# M784new.net
KiCad netlist of a schematic drawn in EAGLE
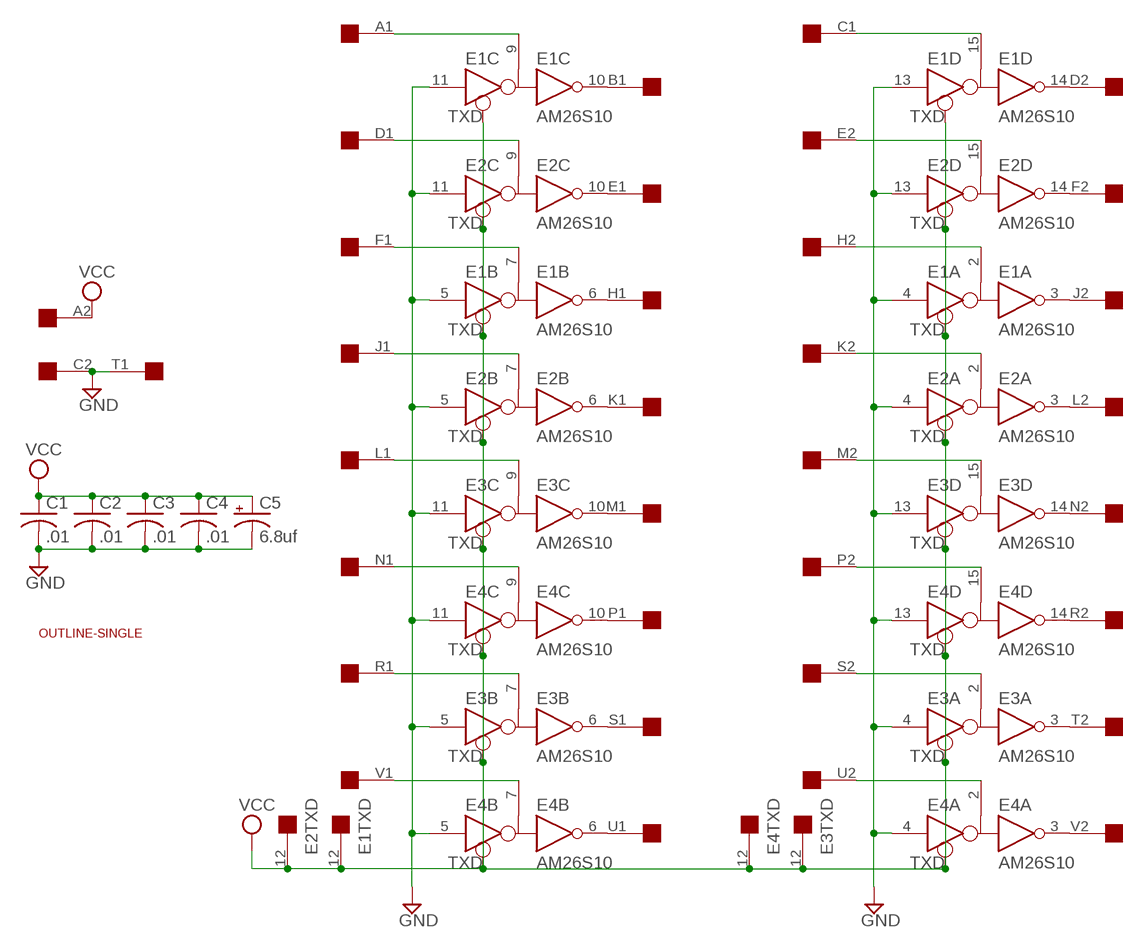
[diagram p0: schematic, sheet 1]

(export (version "E")
  (design (tool "Eeschema 10.0.6"))
  (components
    (comp (ref "C1")
      (value ".01")
      (footprint "eagle-import:C050-025X075")
      (libsource (lib "eagle-import") (part "C-US050-025X075"))
    )
    (comp (ref "C2")
      (value ".01")
      (footprint "eagle-import:C050-025X075")
      (libsource (lib "eagle-import") (part "C-US050-025X075"))
    )
    (comp (ref "C3")
      (value ".01")
      (footprint "eagle-import:C050-025X075")
      (libsource (lib "eagle-import") (part "C-US050-025X075"))
    )
    (comp (ref "C4")
      (value ".01")
      (footprint "eagle-import:C050-025X075")
      (libsource (lib "eagle-import") (part "C-US050-025X075"))
    )
    (comp (ref "C5")
      (value "6.8uf")
      (footprint "eagle-import:E15-5")
      (libsource (lib "eagle-import") (part "CPOL-USE15-5AXIAL"))
    )
    (comp (ref "E1")
      (value "AM26S10")
      (footprint "eagle-import:DIL16")
      (libsource (lib "eagle-import") (part "AM26S10"))
    )
    (comp (ref "E2")
      (value "AM26S10")
      (footprint "eagle-import:DIL16")
      (libsource (lib "eagle-import") (part "AM26S10"))
    )
    (comp (ref "E3")
      (value "AM26S10")
      (footprint "eagle-import:DIL16")
      (libsource (lib "eagle-import") (part "AM26S10"))
    )
    (comp (ref "E4")
      (value "AM26S10")
      (footprint "eagle-import:DIL16")
      (libsource (lib "eagle-import") (part "AM26S10"))
    )
    (comp (ref "U$1")
      (value "SINGLE")
      (footprint "eagle-import:EDGE-CON2")
      (libsource (lib "eagle-import") (part "SINGLE"))
    )
    (comp (ref "U$2")
      (value "OUTLINE-SINGLE")
      (footprint "eagle-import:SINGLE")
      (libsource (lib "eagle-import") (part "OUTLINE-SINGLE"))
    )
  )
  (nets
    (net (code "1") (name "GND") (class "Default")
      (node (ref "C1") (pin "2") (pinfunction "2_2") (pintype "passive"))
      (node (ref "C2") (pin "2") (pinfunction "2_2") (pintype "passive"))
      (node (ref "C3") (pin "2") (pinfunction "2_2") (pintype "passive"))
      (node (ref "C4") (pin "2") (pinfunction "2_2") (pintype "passive"))
      (node (ref "C5") (pin "-") (pinfunction "-_-") (pintype "passive"))
      (node (ref "E1") (pin "11") (pinfunction "D_11") (pintype "input"))
      (node (ref "E1") (pin "13") (pinfunction "D_13") (pintype "input"))
      (node (ref "E1") (pin "4") (pinfunction "D_4") (pintype "input"))
      (node (ref "E1") (pin "5") (pinfunction "D_5") (pintype "input"))
      (node (ref "E2") (pin "11") (pinfunction "D_11") (pintype "input"))
      (node (ref "E2") (pin "13") (pinfunction "D_13") (pintype "input"))
      (node (ref "E2") (pin "4") (pinfunction "D_4") (pintype "input"))
      (node (ref "E2") (pin "5") (pinfunction "D_5") (pintype "input"))
      (node (ref "E3") (pin "11") (pinfunction "D_11") (pintype "input"))
      (node (ref "E3") (pin "13") (pinfunction "D_13") (pintype "input"))
      (node (ref "E3") (pin "4") (pinfunction "D_4") (pintype "input"))
      (node (ref "E3") (pin "5") (pinfunction "D_5") (pintype "input"))
      (node (ref "E4") (pin "11") (pinfunction "D_11") (pintype "input"))
      (node (ref "E4") (pin "13") (pinfunction "D_13") (pintype "input"))
      (node (ref "E4") (pin "4") (pinfunction "D_4") (pintype "input"))
      (node (ref "E4") (pin "5") (pinfunction "D_5") (pintype "input"))
      (node (ref "U$1") (pin "C2") (pinfunction "1_C2") (pintype "bidirectional"))
      (node (ref "U$1") (pin "T1") (pinfunction "1_T1") (pintype "bidirectional"))
    )
    (net (code "2") (name "Net-(E1A-B)") (class "Default")
      (node (ref "E1") (pin "2") (pinfunction "B_2") (pintype "bidirectional"))
      (node (ref "U$1") (pin "H2") (pinfunction "1_H2") (pintype "bidirectional"))
    )
    (net (code "3") (name "Net-(E1A-R)") (class "Default")
      (node (ref "E1") (pin "3") (pinfunction "R_3") (pintype "output"))
      (node (ref "U$1") (pin "J2") (pinfunction "1_J2") (pintype "bidirectional"))
    )
    (net (code "4") (name "Net-(E1B-B)") (class "Default")
      (node (ref "E1") (pin "7") (pinfunction "B_7") (pintype "bidirectional"))
      (node (ref "U$1") (pin "F1") (pinfunction "1_F1") (pintype "bidirectional"))
    )
    (net (code "5") (name "Net-(E1B-R)") (class "Default")
      (node (ref "E1") (pin "6") (pinfunction "R_6") (pintype "output"))
      (node (ref "U$1") (pin "H1") (pinfunction "1_H1") (pintype "bidirectional"))
    )
    (net (code "6") (name "Net-(E1C-B)") (class "Default")
      (node (ref "E1") (pin "9") (pinfunction "B_9") (pintype "bidirectional"))
      (node (ref "U$1") (pin "A1") (pinfunction "1_A1") (pintype "bidirectional"))
    )
    (net (code "7") (name "Net-(E1C-R)") (class "Default")
      (node (ref "E1") (pin "10") (pinfunction "R_10") (pintype "output"))
      (node (ref "U$1") (pin "B1") (pinfunction "1_B1") (pintype "bidirectional"))
    )
    (net (code "8") (name "Net-(E1D-B)") (class "Default")
      (node (ref "E1") (pin "15") (pinfunction "B_15") (pintype "bidirectional"))
      (node (ref "U$1") (pin "C1") (pinfunction "1_C1") (pintype "bidirectional"))
    )
    (net (code "9") (name "Net-(E1D-R)") (class "Default")
      (node (ref "E1") (pin "14") (pinfunction "R_14") (pintype "output"))
      (node (ref "U$1") (pin "D2") (pinfunction "1_D2") (pintype "bidirectional"))
    )
    (net (code "10") (name "Net-(E2A-B)") (class "Default")
      (node (ref "E2") (pin "2") (pinfunction "B_2") (pintype "bidirectional"))
      (node (ref "U$1") (pin "K2") (pinfunction "1_K2") (pintype "bidirectional"))
    )
    (net (code "11") (name "Net-(E2A-R)") (class "Default")
      (node (ref "E2") (pin "3") (pinfunction "R_3") (pintype "output"))
      (node (ref "U$1") (pin "L2") (pinfunction "1_L2") (pintype "bidirectional"))
    )
    (net (code "12") (name "Net-(E2B-B)") (class "Default")
      (node (ref "E2") (pin "7") (pinfunction "B_7") (pintype "bidirectional"))
      (node (ref "U$1") (pin "J1") (pinfunction "1_J1") (pintype "bidirectional"))
    )
    (net (code "13") (name "Net-(E2B-R)") (class "Default")
      (node (ref "E2") (pin "6") (pinfunction "R_6") (pintype "output"))
      (node (ref "U$1") (pin "K1") (pinfunction "1_K1") (pintype "bidirectional"))
    )
    (net (code "14") (name "Net-(E2C-B)") (class "Default")
      (node (ref "E2") (pin "9") (pinfunction "B_9") (pintype "bidirectional"))
      (node (ref "U$1") (pin "D1") (pinfunction "1_D1") (pintype "bidirectional"))
    )
    (net (code "15") (name "Net-(E2C-R)") (class "Default")
      (node (ref "E2") (pin "10") (pinfunction "R_10") (pintype "output"))
      (node (ref "U$1") (pin "E1") (pinfunction "1_E1") (pintype "bidirectional"))
    )
    (net (code "16") (name "Net-(E2D-B)") (class "Default")
      (node (ref "E2") (pin "15") (pinfunction "B_15") (pintype "bidirectional"))
      (node (ref "U$1") (pin "E2") (pinfunction "1_E2") (pintype "bidirectional"))
    )
    (net (code "17") (name "Net-(E2D-R)") (class "Default")
      (node (ref "E2") (pin "14") (pinfunction "R_14") (pintype "output"))
      (node (ref "U$1") (pin "F2") (pinfunction "1_F2") (pintype "bidirectional"))
    )
    (net (code "18") (name "Net-(E3A-B)") (class "Default")
      (node (ref "E3") (pin "2") (pinfunction "B_2") (pintype "bidirectional"))
      (node (ref "U$1") (pin "S2") (pinfunction "1_S2") (pintype "bidirectional"))
    )
    (net (code "19") (name "Net-(E3A-R)") (class "Default")
      (node (ref "E3") (pin "3") (pinfunction "R_3") (pintype "output"))
      (node (ref "U$1") (pin "T2") (pinfunction "1_T2") (pintype "bidirectional"))
    )
    (net (code "20") (name "Net-(E3B-B)") (class "Default")
      (node (ref "E3") (pin "7") (pinfunction "B_7") (pintype "bidirectional"))
      (node (ref "U$1") (pin "R1") (pinfunction "1_R1") (pintype "bidirectional"))
    )
    (net (code "21") (name "Net-(E3B-R)") (class "Default")
      (node (ref "E3") (pin "6") (pinfunction "R_6") (pintype "output"))
      (node (ref "U$1") (pin "S1") (pinfunction "1_S1") (pintype "bidirectional"))
    )
    (net (code "22") (name "Net-(E3C-B)") (class "Default")
      (node (ref "E3") (pin "9") (pinfunction "B_9") (pintype "bidirectional"))
      (node (ref "U$1") (pin "L1") (pinfunction "1_L1") (pintype "bidirectional"))
    )
    (net (code "23") (name "Net-(E3C-R)") (class "Default")
      (node (ref "E3") (pin "10") (pinfunction "R_10") (pintype "output"))
      (node (ref "U$1") (pin "M1") (pinfunction "1_M1") (pintype "bidirectional"))
    )
    (net (code "24") (name "Net-(E3D-B)") (class "Default")
      (node (ref "E3") (pin "15") (pinfunction "B_15") (pintype "bidirectional"))
      (node (ref "U$1") (pin "M2") (pinfunction "1_M2") (pintype "bidirectional"))
    )
    (net (code "25") (name "Net-(E3D-R)") (class "Default")
      (node (ref "E3") (pin "14") (pinfunction "R_14") (pintype "output"))
      (node (ref "U$1") (pin "N2") (pinfunction "1_N2") (pintype "bidirectional"))
    )
    (net (code "26") (name "Net-(E4A-B)") (class "Default")
      (node (ref "E4") (pin "2") (pinfunction "B_2") (pintype "bidirectional"))
      (node (ref "U$1") (pin "U2") (pinfunction "1_U2") (pintype "bidirectional"))
    )
    (net (code "27") (name "Net-(E4A-R)") (class "Default")
      (node (ref "E4") (pin "3") (pinfunction "R_3") (pintype "output"))
      (node (ref "U$1") (pin "V2") (pinfunction "1_V2") (pintype "bidirectional"))
    )
    (net (code "28") (name "Net-(E4B-B)") (class "Default")
      (node (ref "E4") (pin "7") (pinfunction "B_7") (pintype "bidirectional"))
      (node (ref "U$1") (pin "V1") (pinfunction "1_V1") (pintype "bidirectional"))
    )
    (net (code "29") (name "Net-(E4B-R)") (class "Default")
      (node (ref "E4") (pin "6") (pinfunction "R_6") (pintype "output"))
      (node (ref "U$1") (pin "U1") (pinfunction "1_U1") (pintype "bidirectional"))
    )
    (net (code "30") (name "Net-(E4C-B)") (class "Default")
      (node (ref "E4") (pin "9") (pinfunction "B_9") (pintype "bidirectional"))
      (node (ref "U$1") (pin "N1") (pinfunction "1_N1") (pintype "bidirectional"))
    )
    (net (code "31") (name "Net-(E4C-R)") (class "Default")
      (node (ref "E4") (pin "10") (pinfunction "R_10") (pintype "output"))
      (node (ref "U$1") (pin "P1") (pinfunction "1_P1") (pintype "bidirectional"))
    )
    (net (code "32") (name "Net-(E4D-B)") (class "Default")
      (node (ref "E4") (pin "15") (pinfunction "B_15") (pintype "bidirectional"))
      (node (ref "U$1") (pin "P2") (pinfunction "1_P2") (pintype "bidirectional"))
    )
    (net (code "33") (name "Net-(E4D-R)") (class "Default")
      (node (ref "E4") (pin "14") (pinfunction "R_14") (pintype "output"))
      (node (ref "U$1") (pin "R2") (pinfunction "1_R2") (pintype "bidirectional"))
    )
    (net (code "34") (name "VCC") (class "Default")
      (node (ref "C1") (pin "1") (pinfunction "1_1") (pintype "passive"))
      (node (ref "C2") (pin "1") (pinfunction "1_1") (pintype "passive"))
      (node (ref "C3") (pin "1") (pinfunction "1_1") (pintype "passive"))
      (node (ref "C4") (pin "1") (pinfunction "1_1") (pintype "passive"))
      (node (ref "C5") (pin "+") (pinfunction "+_+") (pintype "passive"))
      (node (ref "E1") (pin "12") (pinfunction "TXD_12") (pintype "input"))
      (node (ref "E2") (pin "12") (pinfunction "TXD_12") (pintype "input"))
      (node (ref "E3") (pin "12") (pinfunction "TXD_12") (pintype "input"))
      (node (ref "E4") (pin "12") (pinfunction "TXD_12") (pintype "input"))
      (node (ref "U$1") (pin "A2") (pinfunction "1_A2") (pintype "bidirectional"))
    )
  )
)
